# OvalLedBreakoutForArduino.net
KiCad netlist of a schematic drawn in EAGLE
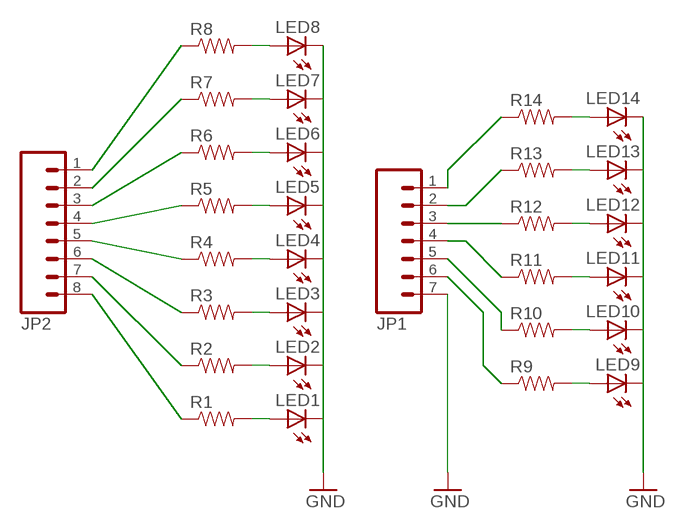
[diagram p0: schematic, sheet 1]

(export (version "E")
  (design (tool "Eeschema 10.0.6"))
  (components
    (comp (ref "JP1")
      (value "M07")
      (footprint "eagle-import:1X07")
      (libsource (lib "eagle-import") (part "M07"))
    )
    (comp (ref "JP2")
      (value "M081X08")
      (footprint "eagle-import:1X08")
      (libsource (lib "eagle-import") (part "M081X08"))
    )
    (comp (ref "LED1")
      (value "LEDOVAL")
      (footprint "eagle-import:LED-OVAL")
      (libsource (lib "eagle-import") (part "LEDOVAL"))
    )
    (comp (ref "LED2")
      (value "LEDOVAL")
      (footprint "eagle-import:LED-OVAL")
      (libsource (lib "eagle-import") (part "LEDOVAL"))
    )
    (comp (ref "LED3")
      (value "LEDOVAL")
      (footprint "eagle-import:LED-OVAL")
      (libsource (lib "eagle-import") (part "LEDOVAL"))
    )
    (comp (ref "LED4")
      (value "LEDOVAL")
      (footprint "eagle-import:LED-OVAL")
      (libsource (lib "eagle-import") (part "LEDOVAL"))
    )
    (comp (ref "LED5")
      (value "LEDOVAL")
      (footprint "eagle-import:LED-OVAL")
      (libsource (lib "eagle-import") (part "LEDOVAL"))
    )
    (comp (ref "LED6")
      (value "LEDOVAL")
      (footprint "eagle-import:LED-OVAL")
      (libsource (lib "eagle-import") (part "LEDOVAL"))
    )
    (comp (ref "LED7")
      (value "LEDOVAL")
      (footprint "eagle-import:LED-OVAL")
      (libsource (lib "eagle-import") (part "LEDOVAL"))
    )
    (comp (ref "LED8")
      (value "LEDOVAL")
      (footprint "eagle-import:LED-OVAL")
      (libsource (lib "eagle-import") (part "LEDOVAL"))
    )
    (comp (ref "LED9")
      (value "LEDOVAL")
      (footprint "eagle-import:LED-OVAL")
      (libsource (lib "eagle-import") (part "LEDOVAL"))
    )
    (comp (ref "LED10")
      (value "LEDOVAL")
      (footprint "eagle-import:LED-OVAL")
      (libsource (lib "eagle-import") (part "LEDOVAL"))
    )
    (comp (ref "LED11")
      (value "LEDOVAL")
      (footprint "eagle-import:LED-OVAL")
      (libsource (lib "eagle-import") (part "LEDOVAL"))
    )
    (comp (ref "LED12")
      (value "LEDOVAL")
      (footprint "eagle-import:LED-OVAL")
      (libsource (lib "eagle-import") (part "LEDOVAL"))
    )
    (comp (ref "LED13")
      (value "LEDOVAL")
      (footprint "eagle-import:LED-OVAL")
      (libsource (lib "eagle-import") (part "LEDOVAL"))
    )
    (comp (ref "LED14")
      (value "LEDOVAL")
      (footprint "eagle-import:LED-OVAL")
      (libsource (lib "eagle-import") (part "LEDOVAL"))
    )
    (comp (ref "R1")
      (value "RESISTORAXIAL-0.3")
      (footprint "eagle-import:AXIAL-0.3")
      (libsource (lib "eagle-import") (part "RESISTORAXIAL-0.3"))
    )
    (comp (ref "R2")
      (value "RESISTORAXIAL-0.3")
      (footprint "eagle-import:AXIAL-0.3")
      (libsource (lib "eagle-import") (part "RESISTORAXIAL-0.3"))
    )
    (comp (ref "R3")
      (value "RESISTORAXIAL-0.3")
      (footprint "eagle-import:AXIAL-0.3")
      (libsource (lib "eagle-import") (part "RESISTORAXIAL-0.3"))
    )
    (comp (ref "R4")
      (value "RESISTORAXIAL-0.3")
      (footprint "eagle-import:AXIAL-0.3")
      (libsource (lib "eagle-import") (part "RESISTORAXIAL-0.3"))
    )
    (comp (ref "R5")
      (value "RESISTORAXIAL-0.3")
      (footprint "eagle-import:AXIAL-0.3")
      (libsource (lib "eagle-import") (part "RESISTORAXIAL-0.3"))
    )
    (comp (ref "R6")
      (value "RESISTORAXIAL-0.3")
      (footprint "eagle-import:AXIAL-0.3")
      (libsource (lib "eagle-import") (part "RESISTORAXIAL-0.3"))
    )
    (comp (ref "R7")
      (value "RESISTORAXIAL-0.3")
      (footprint "eagle-import:AXIAL-0.3")
      (libsource (lib "eagle-import") (part "RESISTORAXIAL-0.3"))
    )
    (comp (ref "R8")
      (value "RESISTORAXIAL-0.3")
      (footprint "eagle-import:AXIAL-0.3")
      (libsource (lib "eagle-import") (part "RESISTORAXIAL-0.3"))
    )
    (comp (ref "R9")
      (value "RESISTORAXIAL-0.3")
      (footprint "eagle-import:AXIAL-0.3")
      (libsource (lib "eagle-import") (part "RESISTORAXIAL-0.3"))
    )
    (comp (ref "R10")
      (value "RESISTORAXIAL-0.3")
      (footprint "eagle-import:AXIAL-0.3")
      (libsource (lib "eagle-import") (part "RESISTORAXIAL-0.3"))
    )
    (comp (ref "R11")
      (value "RESISTORAXIAL-0.3")
      (footprint "eagle-import:AXIAL-0.3")
      (libsource (lib "eagle-import") (part "RESISTORAXIAL-0.3"))
    )
    (comp (ref "R12")
      (value "RESISTORAXIAL-0.3")
      (footprint "eagle-import:AXIAL-0.3")
      (libsource (lib "eagle-import") (part "RESISTORAXIAL-0.3"))
    )
    (comp (ref "R13")
      (value "RESISTORAXIAL-0.3")
      (footprint "eagle-import:AXIAL-0.3")
      (libsource (lib "eagle-import") (part "RESISTORAXIAL-0.3"))
    )
    (comp (ref "R14")
      (value "RESISTORAXIAL-0.3")
      (footprint "eagle-import:AXIAL-0.3")
      (libsource (lib "eagle-import") (part "RESISTORAXIAL-0.3"))
    )
  )
  (nets
    (net (code "1") (name "GND") (class "Default")
      (node (ref "JP1") (pin "7") (pinfunction "7_7") (pintype "passive"))
      (node (ref "LED1") (pin "CATHODE") (pinfunction "C_CATHODE") (pintype "passive"))
      (node (ref "LED10") (pin "CATHODE") (pinfunction "C_CATHODE") (pintype "passive"))
      (node (ref "LED11") (pin "CATHODE") (pinfunction "C_CATHODE") (pintype "passive"))
      (node (ref "LED12") (pin "CATHODE") (pinfunction "C_CATHODE") (pintype "passive"))
      (node (ref "LED13") (pin "CATHODE") (pinfunction "C_CATHODE") (pintype "passive"))
      (node (ref "LED14") (pin "CATHODE") (pinfunction "C_CATHODE") (pintype "passive"))
      (node (ref "LED2") (pin "CATHODE") (pinfunction "C_CATHODE") (pintype "passive"))
      (node (ref "LED3") (pin "CATHODE") (pinfunction "C_CATHODE") (pintype "passive"))
      (node (ref "LED4") (pin "CATHODE") (pinfunction "C_CATHODE") (pintype "passive"))
      (node (ref "LED5") (pin "CATHODE") (pinfunction "C_CATHODE") (pintype "passive"))
      (node (ref "LED6") (pin "CATHODE") (pinfunction "C_CATHODE") (pintype "passive"))
      (node (ref "LED7") (pin "CATHODE") (pinfunction "C_CATHODE") (pintype "passive"))
      (node (ref "LED8") (pin "CATHODE") (pinfunction "C_CATHODE") (pintype "passive"))
      (node (ref "LED9") (pin "CATHODE") (pinfunction "C_CATHODE") (pintype "passive"))
    )
    (net (code "2") (name "Net-(LED1-A)") (class "Default")
      (node (ref "LED1") (pin "ANODE") (pinfunction "A_ANODE") (pintype "passive"))
      (node (ref "R1") (pin "P$2") (pinfunction "2_P$2") (pintype "passive"))
    )
    (net (code "3") (name "Net-(LED2-A)") (class "Default")
      (node (ref "LED2") (pin "ANODE") (pinfunction "A_ANODE") (pintype "passive"))
      (node (ref "R2") (pin "P$2") (pinfunction "2_P$2") (pintype "passive"))
    )
    (net (code "4") (name "Net-(LED3-A)") (class "Default")
      (node (ref "LED3") (pin "ANODE") (pinfunction "A_ANODE") (pintype "passive"))
      (node (ref "R3") (pin "P$2") (pinfunction "2_P$2") (pintype "passive"))
    )
    (net (code "5") (name "Net-(LED4-A)") (class "Default")
      (node (ref "LED4") (pin "ANODE") (pinfunction "A_ANODE") (pintype "passive"))
      (node (ref "R4") (pin "P$2") (pinfunction "2_P$2") (pintype "passive"))
    )
    (net (code "6") (name "Net-(LED5-A)") (class "Default")
      (node (ref "LED5") (pin "ANODE") (pinfunction "A_ANODE") (pintype "passive"))
      (node (ref "R5") (pin "P$2") (pinfunction "2_P$2") (pintype "passive"))
    )
    (net (code "7") (name "Net-(LED6-A)") (class "Default")
      (node (ref "LED6") (pin "ANODE") (pinfunction "A_ANODE") (pintype "passive"))
      (node (ref "R6") (pin "P$2") (pinfunction "2_P$2") (pintype "passive"))
    )
    (net (code "8") (name "Net-(LED7-A)") (class "Default")
      (node (ref "LED7") (pin "ANODE") (pinfunction "A_ANODE") (pintype "passive"))
      (node (ref "R7") (pin "P$2") (pinfunction "2_P$2") (pintype "passive"))
    )
    (net (code "9") (name "Net-(LED8-A)") (class "Default")
      (node (ref "LED8") (pin "ANODE") (pinfunction "A_ANODE") (pintype "passive"))
      (node (ref "R8") (pin "P$2") (pinfunction "2_P$2") (pintype "passive"))
    )
    (net (code "10") (name "Net-(LED9-A)") (class "Default")
      (node (ref "LED9") (pin "ANODE") (pinfunction "A_ANODE") (pintype "passive"))
      (node (ref "R9") (pin "P$2") (pinfunction "2_P$2") (pintype "passive"))
    )
    (net (code "11") (name "Net-(LED10-A)") (class "Default")
      (node (ref "LED10") (pin "ANODE") (pinfunction "A_ANODE") (pintype "passive"))
      (node (ref "R10") (pin "P$2") (pinfunction "2_P$2") (pintype "passive"))
    )
    (net (code "12") (name "Net-(LED11-A)") (class "Default")
      (node (ref "LED11") (pin "ANODE") (pinfunction "A_ANODE") (pintype "passive"))
      (node (ref "R11") (pin "P$2") (pinfunction "2_P$2") (pintype "passive"))
    )
    (net (code "13") (name "Net-(LED12-A)") (class "Default")
      (node (ref "LED12") (pin "ANODE") (pinfunction "A_ANODE") (pintype "passive"))
      (node (ref "R12") (pin "P$2") (pinfunction "2_P$2") (pintype "passive"))
    )
    (net (code "14") (name "Net-(LED13-A)") (class "Default")
      (node (ref "LED13") (pin "ANODE") (pinfunction "A_ANODE") (pintype "passive"))
      (node (ref "R13") (pin "P$2") (pinfunction "2_P$2") (pintype "passive"))
    )
    (net (code "15") (name "Net-(LED14-A)") (class "Default")
      (node (ref "LED14") (pin "ANODE") (pinfunction "A_ANODE") (pintype "passive"))
      (node (ref "R14") (pin "P$2") (pinfunction "2_P$2") (pintype "passive"))
    )
    (net (code "16") (name "Net-(R1-1)") (class "Default")
      (node (ref "JP2") (pin "8") (pinfunction "8_8") (pintype "passive"))
      (node (ref "R1") (pin "P$1") (pinfunction "1_P$1") (pintype "passive"))
    )
    (net (code "17") (name "Net-(R2-1)") (class "Default")
      (node (ref "JP2") (pin "7") (pinfunction "7_7") (pintype "passive"))
      (node (ref "R2") (pin "P$1") (pinfunction "1_P$1") (pintype "passive"))
    )
    (net (code "18") (name "Net-(R3-1)") (class "Default")
      (node (ref "JP2") (pin "6") (pinfunction "6_6") (pintype "passive"))
      (node (ref "R3") (pin "P$1") (pinfunction "1_P$1") (pintype "passive"))
    )
    (net (code "19") (name "Net-(R4-1)") (class "Default")
      (node (ref "JP2") (pin "5") (pinfunction "5_5") (pintype "passive"))
      (node (ref "R4") (pin "P$1") (pinfunction "1_P$1") (pintype "passive"))
    )
    (net (code "20") (name "Net-(R5-1)") (class "Default")
      (node (ref "JP2") (pin "4") (pinfunction "4_4") (pintype "passive"))
      (node (ref "R5") (pin "P$1") (pinfunction "1_P$1") (pintype "passive"))
    )
    (net (code "21") (name "Net-(R6-1)") (class "Default")
      (node (ref "JP2") (pin "3") (pinfunction "3_3") (pintype "passive"))
      (node (ref "R6") (pin "P$1") (pinfunction "1_P$1") (pintype "passive"))
    )
    (net (code "22") (name "Net-(R7-1)") (class "Default")
      (node (ref "JP2") (pin "2") (pinfunction "2_2") (pintype "passive"))
      (node (ref "R7") (pin "P$1") (pinfunction "1_P$1") (pintype "passive"))
    )
    (net (code "23") (name "Net-(R8-1)") (class "Default")
      (node (ref "JP2") (pin "1") (pinfunction "1_1") (pintype "passive"))
      (node (ref "R8") (pin "P$1") (pinfunction "1_P$1") (pintype "passive"))
    )
    (net (code "24") (name "Net-(R9-1)") (class "Default")
      (node (ref "JP1") (pin "6") (pinfunction "6_6") (pintype "passive"))
      (node (ref "R9") (pin "P$1") (pinfunction "1_P$1") (pintype "passive"))
    )
    (net (code "25") (name "Net-(R10-1)") (class "Default")
      (node (ref "JP1") (pin "5") (pinfunction "5_5") (pintype "passive"))
      (node (ref "R10") (pin "P$1") (pinfunction "1_P$1") (pintype "passive"))
    )
    (net (code "26") (name "Net-(R11-1)") (class "Default")
      (node (ref "JP1") (pin "4") (pinfunction "4_4") (pintype "passive"))
      (node (ref "R11") (pin "P$1") (pinfunction "1_P$1") (pintype "passive"))
    )
    (net (code "27") (name "Net-(R12-1)") (class "Default")
      (node (ref "JP1") (pin "3") (pinfunction "3_3") (pintype "passive"))
      (node (ref "R12") (pin "P$1") (pinfunction "1_P$1") (pintype "passive"))
    )
    (net (code "28") (name "Net-(R13-1)") (class "Default")
      (node (ref "JP1") (pin "2") (pinfunction "2_2") (pintype "passive"))
      (node (ref "R13") (pin "P$1") (pinfunction "1_P$1") (pintype "passive"))
    )
    (net (code "29") (name "Net-(R14-1)") (class "Default")
      (node (ref "JP1") (pin "1") (pinfunction "1_1") (pintype "passive"))
      (node (ref "R14") (pin "P$1") (pinfunction "1_P$1") (pintype "passive"))
    )
  )
)
